# Peripherals.net
KiCad netlist of a schematic drawn in Altium Designer
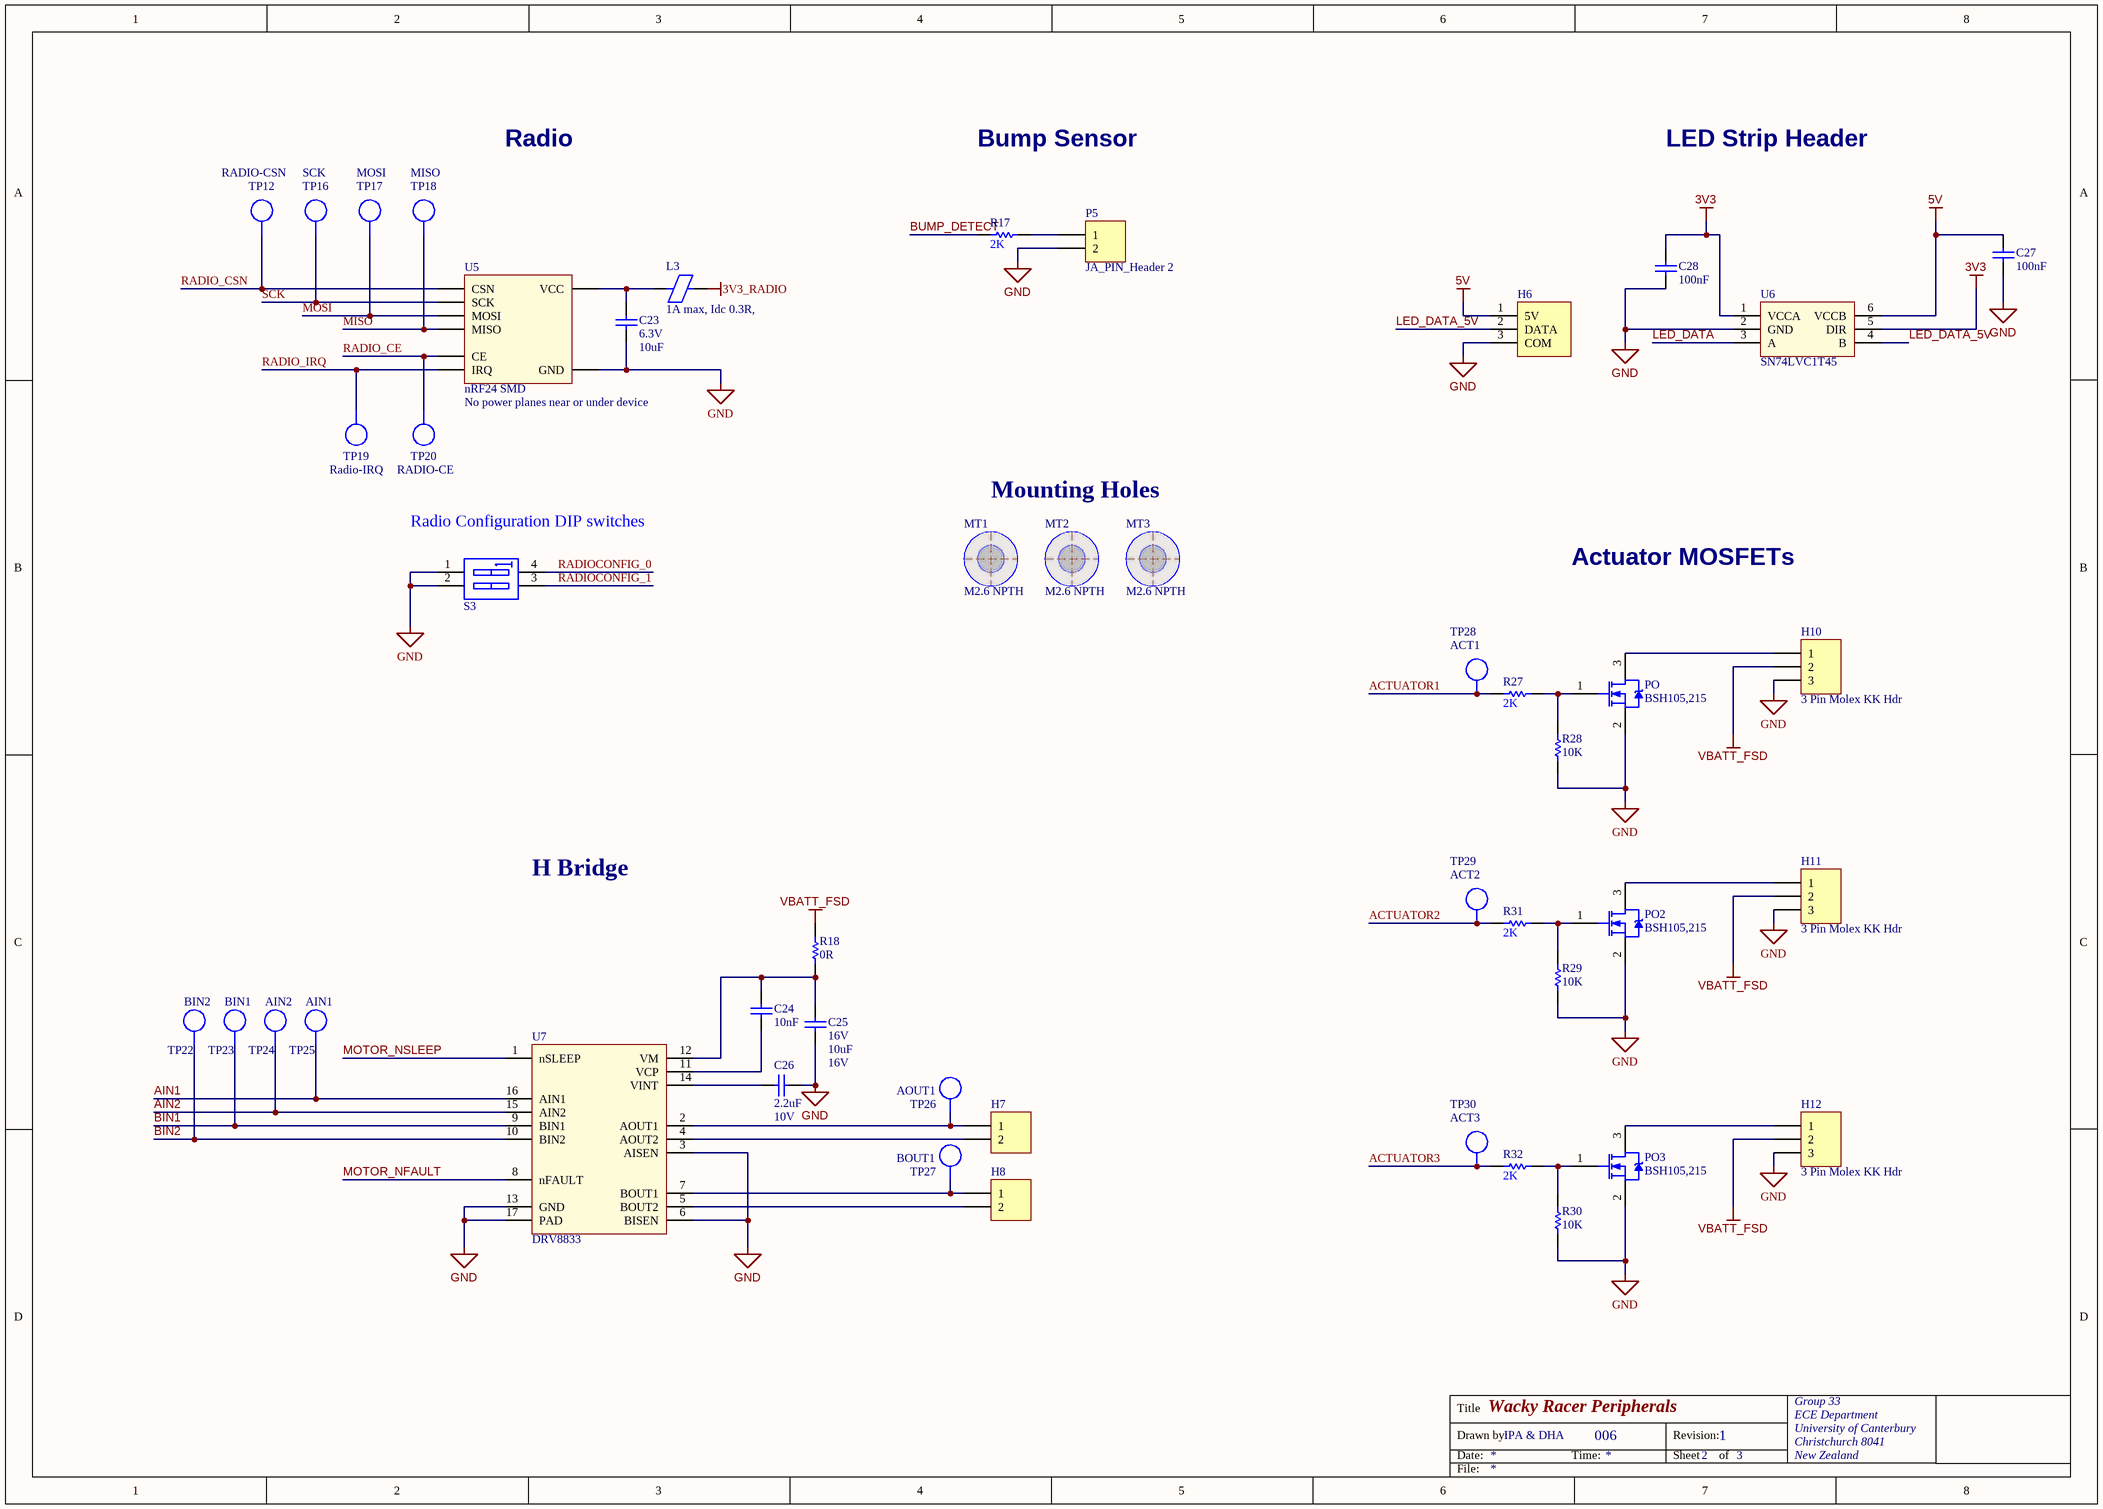
[diagram p0: Peripherals.SchDoc]

(export (version "E")
  (design (tool "Eeschema 10.0.6"))
  (components
    (comp (ref "C23")
      (value "10uF")
      (footprint "CAPC1608L")
      (description "CAP CER 10UF X5R +-20% 6V3 0603")
      (fields (field (name "VOLTAGE - RATED") "6.3V"))
      (libsource (lib "ECE_ComponentsAD23") (part "CC_10uF_0603"))
    )
    (comp (ref "C24")
      (value "10nF")
      (footprint "CAPC1608L")
      (description "CAP CER 10nF X7R +-10% 50V 0603")
      (libsource (lib "ECE_ComponentsAD23") (part "CC_10nF_0603"))
    )
    (comp (ref "C25")
      (value "10uF")
      (footprint "CAPC2012L")
      (description "CAP CER 10uF X5R 16V 0805")
      (fields
        (field (name "MANUFACTURER") "Samsung Electro-Mechanics")
        (field (name "MANUFACTURER PART NUMBER") "CL21A106KOQNNWE")
        (field (name "VOLTAGE - RATED") "16V")
        (field (name "MAX VOLTAGE") "16V")
      )
      (libsource (lib "ECE_ComponentsAD23") (part "CC_10uF_0805_16V"))
    )
    (comp (ref "C26")
      (value "2.2uF")
      (footprint "CAPC1608L")
      (description "CAP CER 2.2uF X5R +-20% 10V 0603")
      (fields (field (name "MAX VOLTAGE") "10V"))
      (libsource (lib "ECE_ComponentsAD23") (part "CC_2.2uF_0603"))
    )
    (comp (ref "C27")
      (value "100nF")
      (footprint "CAPC1608L")
      (description "CAP CER 100nF X7R +-10% 50V 0603")
      (libsource (lib "ECE_ComponentsAD23") (part "CC_100nF_0603"))
    )
    (comp (ref "C28")
      (value "100nF")
      (footprint "CAPC1608L")
      (description "CAP CER 100nF X7R +-10% 50V 0603")
      (libsource (lib "ECE_ComponentsAD23") (part "CC_100nF_0603"))
    )
    (comp (ref "H6")
      (value "3 Pin Molex KK Hdr")
      (footprint "MOLEX_KK_3_HDR")
      (description "CONN HEADER 3POS 2.54mm VERT_Thru Hole")
      (fields (field (name "MANUFACTURER") "Molex"))
      (libsource (lib "ENCE461AD23") (part "LED_Strip_Header"))
    )
    (comp (ref "H7")
      (value "JA_TERM_BLK_HDR_2 PIN")
      (footprint "TMHDR2")
      (description "TERM_BLK_HEADER 5.08mm 2 Pos R/A Thru Hole")
      (fields
        (field (name "MANUFACTURER") "Phoenix Contact")
        (field (name "MANUFACTURER PART NUMBER") "1727010")
      )
      (libsource (lib "ECE_ComponentsAD23") (part "JA_TERM_BLK_HDR_2 PIN"))
    )
    (comp (ref "H8")
      (value "JA_TERM_BLK_HDR_2 PIN")
      (footprint "TMHDR2")
      (description "TERM_BLK_HEADER 5.08mm 2 Pos R/A Thru Hole")
      (fields
        (field (name "MANUFACTURER") "Phoenix Contact")
        (field (name "MANUFACTURER PART NUMBER") "1727010")
      )
      (libsource (lib "ECE_ComponentsAD23") (part "JA_TERM_BLK_HDR_2 PIN"))
    )
    (comp (ref "H10")
      (value "3 Pin Molex KK Hdr")
      (footprint "MOLEX_KK_3_HDR")
      (description "CONN HEADER 3POS 2.54mm VERT_Thru Hole")
      (fields (field (name "MANUFACTURER") "Molex"))
      (libsource (lib "ECE_ComponentsAD23") (part "JA_MOLEX_KK_3POS"))
    )
    (comp (ref "H11")
      (value "3 Pin Molex KK Hdr")
      (footprint "MOLEX_KK_3_HDR")
      (description "CONN HEADER 3POS 2.54mm VERT_Thru Hole")
      (fields (field (name "MANUFACTURER") "Molex"))
      (libsource (lib "ECE_ComponentsAD23") (part "JA_MOLEX_KK_3POS"))
    )
    (comp (ref "H12")
      (value "3 Pin Molex KK Hdr")
      (footprint "MOLEX_KK_3_HDR")
      (description "CONN HEADER 3POS 2.54mm VERT_Thru Hole")
      (fields (field (name "MANUFACTURER") "Molex"))
      (libsource (lib "ECE_ComponentsAD23") (part "JA_MOLEX_KK_3POS"))
    )
    (comp (ref "L3")
      (value "1A max, Idc 0.3R,")
      (footprint "INDC3216L")
      (description "Ferrite Bead, Rdc 0.3R, Z100MHZ 600R, Imax 1A, SMD 1206")
      (fields
        (field (name "MANUFACTURER") "FAIR-RITE")
        (field (name "MANUFACTURER PART NUMBER") "2512066017Y1")
      )
      (libsource (lib "ECE_ComponentsAD23") (part "IN_Ferrite-Bead"))
    )
    (comp (ref "MT1")
      (value "M2.6 NPTH")
      (footprint "MNT-HOLE_2.6mm_NPTH")
      (description "Fixing M2.6 Mount Hole NPTH")
      (fields (field (name "MANUFACTURER") "Hi-Q"))
      (libsource (lib "ECE_ComponentsAD23") (part "MC_M2.6_HOLE"))
    )
    (comp (ref "MT2")
      (value "M2.6 NPTH")
      (footprint "MNT-HOLE_2.6mm_NPTH")
      (description "Fixing M2.6 Mount Hole NPTH")
      (fields (field (name "MANUFACTURER") "Hi-Q"))
      (libsource (lib "ECE_ComponentsAD23") (part "MC_M2.6_HOLE"))
    )
    (comp (ref "MT3")
      (value "M2.6 NPTH")
      (footprint "MNT-HOLE_2.6mm_NPTH")
      (description "Fixing M2.6 Mount Hole NPTH")
      (fields (field (name "MANUFACTURER") "Hi-Q"))
      (libsource (lib "ECE_ComponentsAD23") (part "MC_M2.6_HOLE"))
    )
    (comp (ref "P5")
      (value "JA_PIN_Header 2")
      (footprint "HDR1X2")
      (description "Header, 2-Pin")
      (fields (field (name "PUBLISHER") "Altium Limited"))
      (libsource (lib "ECE_ComponentsAD23") (part "JA_PIN_Header 2"))
    )
    (comp (ref "PO")
      (value "BSH105,215")
      (footprint "SOT23_L")
      (description "MOSFET N-CH 20V 1.05A SOT-23")
      (fields
        (field (name "MANUFACTURER") "NXP Semiconductors")
        (field (name "MANUFACTURER PART NUMBER") "BSH105,215")
      )
      (libsource (lib "ECE_ComponentsAD23") (part "TM_BSH105"))
    )
    (comp (ref "PO2")
      (value "BSH105,215")
      (footprint "SOT23_L")
      (description "MOSFET N-CH 20V 1.05A SOT-23")
      (fields
        (field (name "MANUFACTURER") "NXP Semiconductors")
        (field (name "MANUFACTURER PART NUMBER") "BSH105,215")
      )
      (libsource (lib "ECE_ComponentsAD23") (part "TM_BSH105"))
    )
    (comp (ref "PO3")
      (value "BSH105,215")
      (footprint "SOT23_L")
      (description "MOSFET N-CH 20V 1.05A SOT-23")
      (fields
        (field (name "MANUFACTURER") "NXP Semiconductors")
        (field (name "MANUFACTURER PART NUMBER") "BSH105,215")
      )
      (libsource (lib "ECE_ComponentsAD23") (part "TM_BSH105"))
    )
    (comp (ref "R17")
      (value "2K")
      (footprint "RESC1608L")
      (description "RES 2K OHM 1/10W 5% 0603 SMD")
      (libsource (lib "ECE_ComponentsAD23") (part "RS_2K"))
    )
    (comp (ref "R18")
      (value "0R")
      (footprint "RESC3216L")
      (description "RES 0R OHM 1/8W 5% 1206 SMD")
      (libsource (lib "ECE_ComponentsAD23") (part "RT_0R"))
    )
    (comp (ref "R27")
      (value "2K")
      (footprint "RESC1608L")
      (description "RES 2K OHM 1/10W 5% 0603 SMD")
      (libsource (lib "ECE_ComponentsAD23") (part "RS_2K"))
    )
    (comp (ref "R28")
      (value "10K")
      (footprint "RESC1608L")
      (description "RES 10.0K OHM 1/10W 5% 0603 SMD")
      (libsource (lib "ECE_ComponentsAD23") (part "RS_10K"))
    )
    (comp (ref "R29")
      (value "10K")
      (footprint "RESC1608L")
      (description "RES 10.0K OHM 1/10W 5% 0603 SMD")
      (libsource (lib "ECE_ComponentsAD23") (part "RS_10K"))
    )
    (comp (ref "R30")
      (value "10K")
      (footprint "RESC1608L")
      (description "RES 10.0K OHM 1/10W 5% 0603 SMD")
      (libsource (lib "ECE_ComponentsAD23") (part "RS_10K"))
    )
    (comp (ref "R31")
      (value "2K")
      (footprint "RESC1608L")
      (description "RES 2K OHM 1/10W 5% 0603 SMD")
      (libsource (lib "ECE_ComponentsAD23") (part "RS_2K"))
    )
    (comp (ref "R32")
      (value "2K")
      (footprint "RESC1608L")
      (description "RES 2K OHM 1/10W 5% 0603 SMD")
      (libsource (lib "ECE_ComponentsAD23") (part "RS_2K"))
    )
    (comp (ref "S3")
      (value "WS_SW DIP-2")
      (footprint "DIP_SW_2WAY_SMD")
      (description "DIP Switch, 2 Position, SPST SMD")
      (fields
        (field (name "MANUFACTURER") "OMRON ELECTRONIC COMPONENTS")
        (field (name "MANUFACTURER PART NUMBER") "A6SN-2101")
      )
      (libsource (lib "ECE_ComponentsAD23") (part "WS_SW DIP-2"))
    )
    (comp (ref "TP12")
      (value "RADIO-CSN")
      (footprint "TP_1206")
      (description "Test-Point 3.3x1.6x2.1mm SMD")
      (fields
        (field (name "MANUFACTURER") "Harwin Inc")
        (field (name "MANUFACTURER PART NUMBER") "S1751-46R")
      )
      (libsource (lib "ECE_ComponentsAD23") (part "TP_1206"))
    )
    (comp (ref "TP16")
      (value "SCK")
      (footprint "TP_1206")
      (description "Test-Point 3.3x1.6x2.1mm SMD")
      (fields
        (field (name "MANUFACTURER") "Harwin Inc")
        (field (name "MANUFACTURER PART NUMBER") "S1751-46R")
      )
      (libsource (lib "ECE_ComponentsAD23") (part "TP_1206"))
    )
    (comp (ref "TP17")
      (value "MOSI")
      (footprint "TP_1206")
      (description "Test-Point 3.3x1.6x2.1mm SMD")
      (fields
        (field (name "MANUFACTURER") "Harwin Inc")
        (field (name "MANUFACTURER PART NUMBER") "S1751-46R")
      )
      (libsource (lib "ECE_ComponentsAD23") (part "TP_1206"))
    )
    (comp (ref "TP18")
      (value "MISO")
      (footprint "TP_1206")
      (description "Test-Point 3.3x1.6x2.1mm SMD")
      (fields
        (field (name "MANUFACTURER") "Harwin Inc")
        (field (name "MANUFACTURER PART NUMBER") "S1751-46R")
      )
      (libsource (lib "ECE_ComponentsAD23") (part "TP_1206"))
    )
    (comp (ref "TP19")
      (value "Radio-IRQ")
      (footprint "TP_1206")
      (description "Test-Point 3.3x1.6x2.1mm SMD")
      (fields
        (field (name "MANUFACTURER") "Harwin Inc")
        (field (name "MANUFACTURER PART NUMBER") "S1751-46R")
      )
      (libsource (lib "ECE_ComponentsAD23") (part "TP_1206"))
    )
    (comp (ref "TP20")
      (value "RADIO-CE")
      (footprint "TP_1206")
      (description "Test-Point 3.3x1.6x2.1mm SMD")
      (fields
        (field (name "MANUFACTURER") "Harwin Inc")
        (field (name "MANUFACTURER PART NUMBER") "S1751-46R")
      )
      (libsource (lib "ECE_ComponentsAD23") (part "TP_1206"))
    )
    (comp (ref "TP22")
      (value "BIN2")
      (footprint "TP_1206")
      (description "Test-Point 3.3x1.6x2.1mm SMD")
      (fields
        (field (name "MANUFACTURER") "Harwin Inc")
        (field (name "MANUFACTURER PART NUMBER") "S1751-46R")
      )
      (libsource (lib "ECE_ComponentsAD23") (part "TP_1206"))
    )
    (comp (ref "TP23")
      (value "BIN1")
      (footprint "TP_1206")
      (description "Test-Point 3.3x1.6x2.1mm SMD")
      (fields
        (field (name "MANUFACTURER") "Harwin Inc")
        (field (name "MANUFACTURER PART NUMBER") "S1751-46R")
      )
      (libsource (lib "ECE_ComponentsAD23") (part "TP_1206"))
    )
    (comp (ref "TP24")
      (value "AIN2")
      (footprint "TP_1206")
      (description "Test-Point 3.3x1.6x2.1mm SMD")
      (fields
        (field (name "MANUFACTURER") "Harwin Inc")
        (field (name "MANUFACTURER PART NUMBER") "S1751-46R")
      )
      (libsource (lib "ECE_ComponentsAD23") (part "TP_1206"))
    )
    (comp (ref "TP25")
      (value "AIN1")
      (footprint "TP_1206")
      (description "Test-Point 3.3x1.6x2.1mm SMD")
      (fields
        (field (name "MANUFACTURER") "Harwin Inc")
        (field (name "MANUFACTURER PART NUMBER") "S1751-46R")
      )
      (libsource (lib "ECE_ComponentsAD23") (part "TP_1206"))
    )
    (comp (ref "TP26")
      (value "AOUT1")
      (footprint "TP_1206")
      (description "Test-Point 3.3x1.6x2.1mm SMD")
      (fields
        (field (name "MANUFACTURER") "Harwin Inc")
        (field (name "MANUFACTURER PART NUMBER") "S1751-46R")
      )
      (libsource (lib "ECE_ComponentsAD23") (part "TP_1206"))
    )
    (comp (ref "TP27")
      (value "BOUT1")
      (footprint "TP_1206")
      (description "Test-Point 3.3x1.6x2.1mm SMD")
      (fields
        (field (name "MANUFACTURER") "Harwin Inc")
        (field (name "MANUFACTURER PART NUMBER") "S1751-46R")
      )
      (libsource (lib "ECE_ComponentsAD23") (part "TP_1206"))
    )
    (comp (ref "TP28")
      (value "ACT1")
      (footprint "TP_1206")
      (description "Test-Point 3.3x1.6x2.1mm SMD")
      (fields
        (field (name "MANUFACTURER") "Harwin Inc")
        (field (name "MANUFACTURER PART NUMBER") "S1751-46R")
      )
      (libsource (lib "ECE_ComponentsAD23") (part "TP_1206"))
    )
    (comp (ref "TP29")
      (value "ACT2")
      (footprint "TP_1206")
      (description "Test-Point 3.3x1.6x2.1mm SMD")
      (fields
        (field (name "MANUFACTURER") "Harwin Inc")
        (field (name "MANUFACTURER PART NUMBER") "S1751-46R")
      )
      (libsource (lib "ECE_ComponentsAD23") (part "TP_1206"))
    )
    (comp (ref "TP30")
      (value "ACT3")
      (footprint "TP_1206")
      (description "Test-Point 3.3x1.6x2.1mm SMD")
      (fields
        (field (name "MANUFACTURER") "Harwin Inc")
        (field (name "MANUFACTURER PART NUMBER") "S1751-46R")
      )
      (libsource (lib "ECE_ComponentsAD23") (part "TP_1206"))
    )
    (comp (ref "U5")
      (value "nRF24 SMD")
      (footprint "NRF24")
      (description "nRF24 SMD Module")
      (fields (field (name "WARNING") "No power planes near or under device"))
      (libsource (lib "ENCE461AD23") (part "NRF24"))
    )
    (comp (ref "U6")
      (value "SN74LVC1T45")
      (footprint "SOT23-6_N")
      (description "1.8V - 5V level converter")
      (libsource (lib "ENCE461AD23") (part "SN74LVC1T45"))
    )
    (comp (ref "U7")
      (value "DRV8833")
      (footprint "HTSOP16 DRV8833")
      (description "Dual H-Bridge Motor Driver 1.5A")
      (libsource (lib "ENCE461AD23") (part "DRV8833"))
    )
  )
  (nets
    (net (code "1") (name "/ACTUATOR1") (class "Default")
      (node (ref "R27") (pin "1") (pinfunction "1_1") (pintype "passive"))
      (node (ref "TP28") (pin "1") (pinfunction "1_1") (pintype "passive"))
    )
    (net (code "2") (name "/ACTUATOR2") (class "Default")
      (node (ref "R31") (pin "1") (pinfunction "1_1") (pintype "passive"))
      (node (ref "TP29") (pin "1") (pinfunction "1_1") (pintype "passive"))
    )
    (net (code "3") (name "/ACTUATOR3") (class "Default")
      (node (ref "R32") (pin "1") (pinfunction "1_1") (pintype "passive"))
      (node (ref "TP30") (pin "1") (pinfunction "1_1") (pintype "passive"))
    )
    (net (code "4") (name "/AIN1") (class "Default")
      (node (ref "TP25") (pin "1") (pinfunction "1_1") (pintype "passive"))
      (node (ref "U7") (pin "16") (pinfunction "AIN1_16") (pintype "passive"))
    )
    (net (code "5") (name "/AIN2") (class "Default")
      (node (ref "TP24") (pin "1") (pinfunction "1_1") (pintype "passive"))
      (node (ref "U7") (pin "15") (pinfunction "AIN2_15") (pintype "passive"))
    )
    (net (code "6") (name "/BIN1") (class "Default")
      (node (ref "TP23") (pin "1") (pinfunction "1_1") (pintype "passive"))
      (node (ref "U7") (pin "9") (pinfunction "BIN1_9") (pintype "passive"))
    )
    (net (code "7") (name "/BIN2") (class "Default")
      (node (ref "TP22") (pin "1") (pinfunction "1_1") (pintype "passive"))
      (node (ref "U7") (pin "10") (pinfunction "BIN2_10") (pintype "passive"))
    )
    (net (code "8") (name "/BUMP_DETECT") (class "Default")
      (node (ref "R17") (pin "1") (pinfunction "1_1") (pintype "passive"))
    )
    (net (code "9") (name "/LED_DATA") (class "Default")
      (node (ref "U6") (pin "3") (pinfunction "A_3") (pintype "passive"))
    )
    (net (code "10") (name "/LED_DATA_5V") (class "Default")
      (node (ref "H6") (pin "2") (pinfunction "DATA_2") (pintype "passive"))
      (node (ref "U6") (pin "4") (pinfunction "B_4") (pintype "passive"))
    )
    (net (code "11") (name "/MISO") (class "Default")
      (node (ref "TP18") (pin "1") (pinfunction "1_1") (pintype "passive"))
      (node (ref "U5") (pin "7") (pinfunction "MISO_7") (pintype "passive"))
    )
    (net (code "12") (name "/MOSI") (class "Default")
      (node (ref "TP17") (pin "1") (pinfunction "1_1") (pintype "passive"))
      (node (ref "U5") (pin "6") (pinfunction "MOSI_6") (pintype "passive"))
    )
    (net (code "13") (name "/MOTOR_NFAULT") (class "Default")
      (node (ref "U7") (pin "8") (pinfunction "nFAULT_8") (pintype "passive"))
    )
    (net (code "14") (name "/MOTOR_NSLEEP") (class "Default")
      (node (ref "U7") (pin "1") (pinfunction "nSLEEP_1") (pintype "passive"))
    )
    (net (code "15") (name "/RADIOCONFIG_0") (class "Default")
      (node (ref "S3") (pin "4") (pinfunction "B1_4") (pintype "passive"))
    )
    (net (code "16") (name "/RADIOCONFIG_1") (class "Default")
      (node (ref "S3") (pin "3") (pinfunction "B2_3") (pintype "passive"))
    )
    (net (code "17") (name "/RADIO_CE") (class "Default")
      (node (ref "TP20") (pin "1") (pinfunction "1_1") (pintype "passive"))
      (node (ref "U5") (pin "3") (pinfunction "CE_3") (pintype "passive"))
    )
    (net (code "18") (name "/RADIO_CSN") (class "Default")
      (node (ref "TP12") (pin "1") (pinfunction "1_1") (pintype "passive"))
      (node (ref "U5") (pin "4") (pinfunction "CSN_4") (pintype "passive"))
    )
    (net (code "19") (name "/RADIO_IRQ") (class "Default")
      (node (ref "TP19") (pin "1") (pinfunction "1_1") (pintype "passive"))
      (node (ref "U5") (pin "8") (pinfunction "IRQ_8") (pintype "passive"))
    )
    (net (code "20") (name "/SCK") (class "Default")
      (node (ref "TP16") (pin "1") (pinfunction "1_1") (pintype "passive"))
      (node (ref "U5") (pin "5") (pinfunction "SCK_5") (pintype "passive"))
    )
    (net (code "21") (name "3V3") (class "Default")
      (node (ref "C28") (pin "2") (pinfunction "2_2") (pintype "passive"))
      (node (ref "U6") (pin "1") (pinfunction "VCCA_1") (pintype "passive"))
      (node (ref "U6") (pin "5") (pinfunction "DIR_5") (pintype "passive"))
    )
    (net (code "22") (name "3V3_RADIO") (class "Default")
      (node (ref "L3") (pin "2") (pinfunction "2_2") (pintype "passive"))
    )
    (net (code "23") (name "5V") (class "Default")
      (node (ref "C27") (pin "2") (pinfunction "2_2") (pintype "passive"))
      (node (ref "H6") (pin "1") (pinfunction "5V_1") (pintype "passive"))
      (node (ref "U6") (pin "6") (pinfunction "VCCB_6") (pintype "passive"))
    )
    (net (code "24") (name "GND") (class "Default")
      (node (ref "C23") (pin "1") (pinfunction "1_1") (pintype "passive"))
      (node (ref "C25") (pin "1") (pinfunction "1_1") (pintype "passive"))
      (node (ref "C26") (pin "2") (pinfunction "2_2") (pintype "passive"))
      (node (ref "C27") (pin "1") (pinfunction "1_1") (pintype "passive"))
      (node (ref "C28") (pin "1") (pinfunction "1_1") (pintype "passive"))
      (node (ref "H10") (pin "3") (pinfunction "3_3") (pintype "passive"))
      (node (ref "H11") (pin "3") (pinfunction "3_3") (pintype "passive"))
      (node (ref "H12") (pin "3") (pinfunction "3_3") (pintype "passive"))
      (node (ref "H6") (pin "3") (pinfunction "COM_3") (pintype "passive"))
      (node (ref "P5") (pin "2") (pinfunction "2_2") (pintype "passive"))
      (node (ref "PO") (pin "2") (pinfunction "2_2") (pintype "passive"))
      (node (ref "PO2") (pin "2") (pinfunction "2_2") (pintype "passive"))
      (node (ref "PO3") (pin "2") (pinfunction "2_2") (pintype "passive"))
      (node (ref "R28") (pin "1") (pinfunction "1_1") (pintype "passive"))
      (node (ref "R29") (pin "1") (pinfunction "1_1") (pintype "passive"))
      (node (ref "R30") (pin "1") (pinfunction "1_1") (pintype "passive"))
      (node (ref "S3") (pin "1") (pinfunction "A1_1") (pintype "passive"))
      (node (ref "S3") (pin "2") (pinfunction "A2_2") (pintype "passive"))
      (node (ref "U5") (pin "2") (pinfunction "GND_2") (pintype "passive"))
      (node (ref "U6") (pin "2") (pinfunction "GND_2") (pintype "passive"))
      (node (ref "U7") (pin "13") (pinfunction "GND_13") (pintype "passive"))
      (node (ref "U7") (pin "17") (pinfunction "PAD_17") (pintype "passive"))
      (node (ref "U7") (pin "3") (pinfunction "AISEN_3") (pintype "passive"))
      (node (ref "U7") (pin "6") (pinfunction "BISEN_6") (pintype "passive"))
    )
    (net (code "25") (name "Net-(H10-Pad1)") (class "Default")
      (node (ref "H10") (pin "1") (pinfunction "1_1") (pintype "passive"))
      (node (ref "PO") (pin "3") (pinfunction "3_3") (pintype "passive"))
    )
    (net (code "26") (name "Net-(H11-Pad1)") (class "Default")
      (node (ref "H11") (pin "1") (pinfunction "1_1") (pintype "passive"))
      (node (ref "PO2") (pin "3") (pinfunction "3_3") (pintype "passive"))
    )
    (net (code "27") (name "Net-(H12-Pad1)") (class "Default")
      (node (ref "H12") (pin "1") (pinfunction "1_1") (pintype "passive"))
      (node (ref "PO3") (pin "3") (pinfunction "3_3") (pintype "passive"))
    )
    (net (code "28") (name "Net-(P5-Pad1)") (class "Default")
      (node (ref "P5") (pin "1") (pinfunction "1_1") (pintype "passive"))
      (node (ref "R17") (pin "2") (pinfunction "2_2") (pintype "passive"))
    )
    (net (code "29") (name "Net-(PO-Pad1)") (class "Default")
      (node (ref "PO") (pin "1") (pinfunction "1_1") (pintype "passive"))
      (node (ref "R27") (pin "2") (pinfunction "2_2") (pintype "passive"))
      (node (ref "R28") (pin "2") (pinfunction "2_2") (pintype "passive"))
    )
    (net (code "30") (name "Net-(PO2-Pad1)") (class "Default")
      (node (ref "PO2") (pin "1") (pinfunction "1_1") (pintype "passive"))
      (node (ref "R29") (pin "2") (pinfunction "2_2") (pintype "passive"))
      (node (ref "R31") (pin "2") (pinfunction "2_2") (pintype "passive"))
    )
    (net (code "31") (name "Net-(PO3-Pad1)") (class "Default")
      (node (ref "PO3") (pin "1") (pinfunction "1_1") (pintype "passive"))
      (node (ref "R30") (pin "2") (pinfunction "2_2") (pintype "passive"))
      (node (ref "R32") (pin "2") (pinfunction "2_2") (pintype "passive"))
    )
    (net (code "32") (name "Net-(U5-VCC)") (class "Default")
      (node (ref "C23") (pin "2") (pinfunction "2_2") (pintype "passive"))
      (node (ref "L3") (pin "1") (pinfunction "1_1") (pintype "passive"))
      (node (ref "U5") (pin "1") (pinfunction "VCC_1") (pintype "passive"))
    )
    (net (code "33") (name "Net-(U7-AOUT1)") (class "Default")
      (node (ref "H7") (pin "1") (pinfunction "1_1") (pintype "passive"))
      (node (ref "TP26") (pin "1") (pinfunction "1_1") (pintype "passive"))
      (node (ref "U7") (pin "2") (pinfunction "AOUT1_2") (pintype "passive"))
    )
    (net (code "34") (name "Net-(U7-AOUT2)") (class "Default")
      (node (ref "H7") (pin "2") (pinfunction "2_2") (pintype "passive"))
      (node (ref "U7") (pin "4") (pinfunction "AOUT2_4") (pintype "passive"))
    )
    (net (code "35") (name "Net-(U7-BOUT1)") (class "Default")
      (node (ref "H8") (pin "1") (pinfunction "1_1") (pintype "passive"))
      (node (ref "TP27") (pin "1") (pinfunction "1_1") (pintype "passive"))
      (node (ref "U7") (pin "7") (pinfunction "BOUT1_7") (pintype "passive"))
    )
    (net (code "36") (name "Net-(U7-BOUT2)") (class "Default")
      (node (ref "H8") (pin "2") (pinfunction "2_2") (pintype "passive"))
      (node (ref "U7") (pin "5") (pinfunction "BOUT2_5") (pintype "passive"))
    )
    (net (code "37") (name "Net-(U7-VCP)") (class "Default")
      (node (ref "C24") (pin "1") (pinfunction "1_1") (pintype "passive"))
      (node (ref "U7") (pin "11") (pinfunction "VCP_11") (pintype "passive"))
    )
    (net (code "38") (name "Net-(U7-VINT)") (class "Default")
      (node (ref "C26") (pin "1") (pinfunction "1_1") (pintype "passive"))
      (node (ref "U7") (pin "14") (pinfunction "VINT_14") (pintype "passive"))
    )
    (net (code "39") (name "Net-(U7-VM)") (class "Default")
      (node (ref "C24") (pin "2") (pinfunction "2_2") (pintype "passive"))
      (node (ref "C25") (pin "2") (pinfunction "2_2") (pintype "passive"))
      (node (ref "R18") (pin "1") (pinfunction "1_1") (pintype "passive"))
      (node (ref "U7") (pin "12") (pinfunction "VM_12") (pintype "passive"))
    )
    (net (code "40") (name "VBATT_FSD") (class "Default")
      (node (ref "H10") (pin "2") (pinfunction "2_2") (pintype "passive"))
      (node (ref "H11") (pin "2") (pinfunction "2_2") (pintype "passive"))
      (node (ref "H12") (pin "2") (pinfunction "2_2") (pintype "passive"))
      (node (ref "R18") (pin "2") (pinfunction "2_2") (pintype "passive"))
    )
  )
)
